# lpc_serial.net
KiCad netlist of a schematic drawn in EAGLE
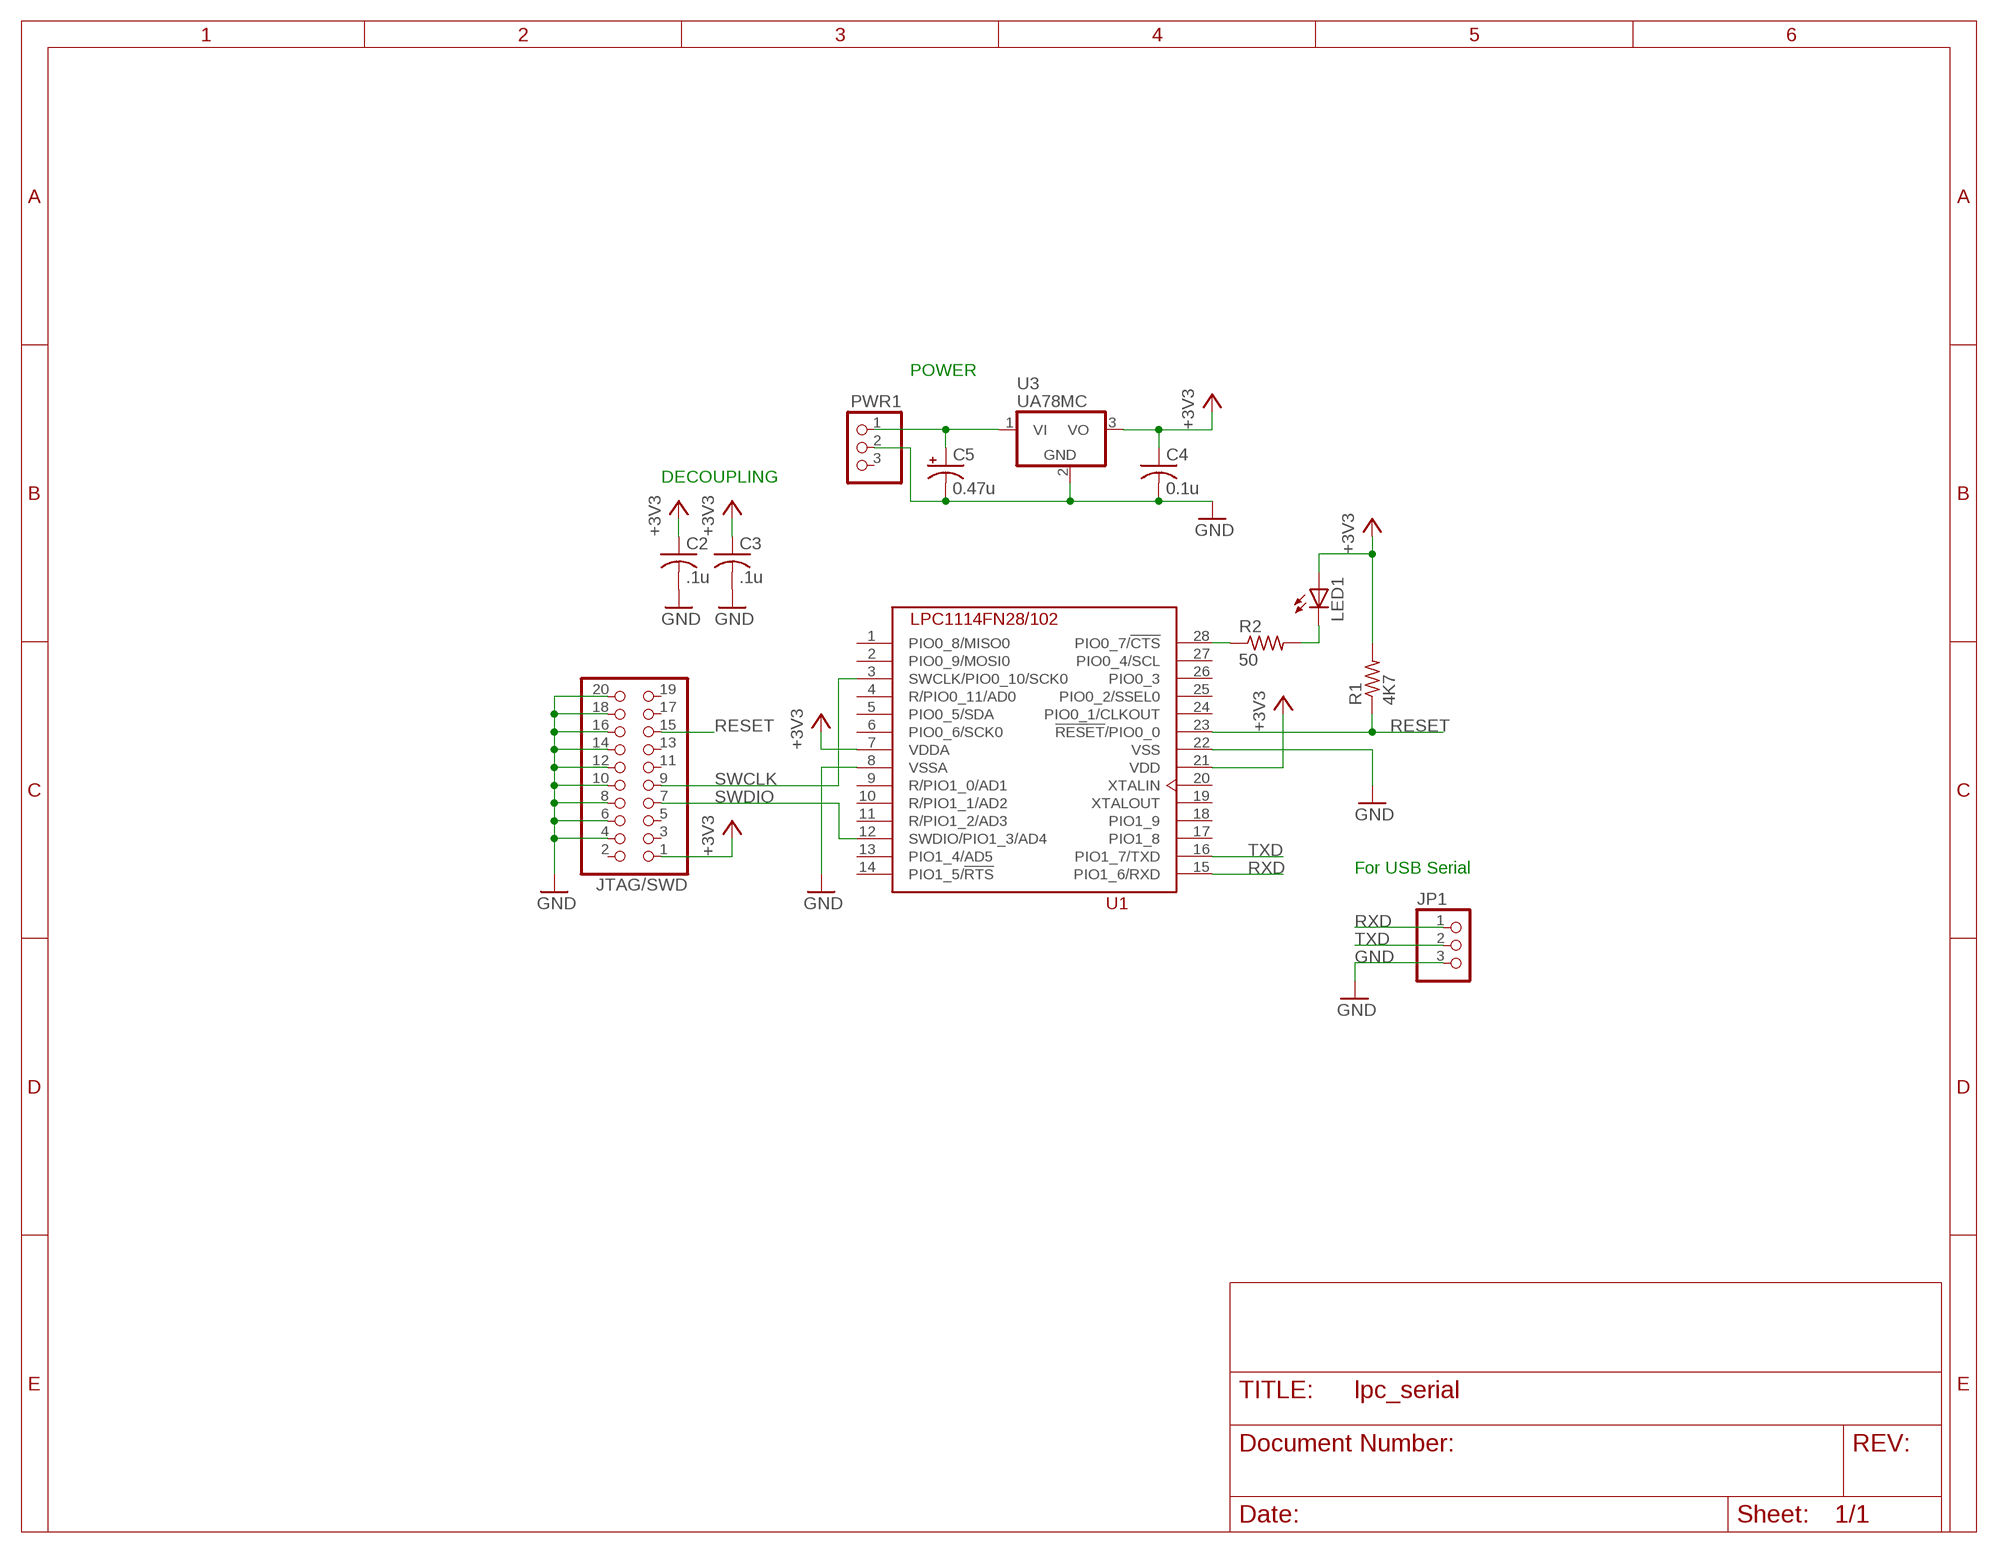
[diagram p0: schematic, sheet 1]

(export (version "E")
  (design (tool "Eeschema 10.0.6"))
  (components
    (comp (ref "C2")
      (value ".1u")
      (footprint "eagle-import:C050-024X044")
      (libsource (lib "eagle-import") (part "C-US050-024X044"))
    )
    (comp (ref "C3")
      (value ".1u")
      (footprint "eagle-import:C050-024X044")
      (libsource (lib "eagle-import") (part "C-US050-024X044"))
    )
    (comp (ref "C4")
      (value "0.1u")
      (footprint "eagle-import:C050-024X044")
      (libsource (lib "eagle-import") (part "C-US050-024X044"))
    )
    (comp (ref "C5")
      (value "0.47u")
      (footprint "eagle-import:E2-5")
      (libsource (lib "eagle-import") (part "CPOL-USE2-5"))
    )
    (comp (ref "JP1")
      (value "PINHD-1X3")
      (footprint "eagle-import:1X03")
      (libsource (lib "eagle-import") (part "PINHD-1X3"))
    )
    (comp (ref "JTAG/SWD")
      (value "PINHD-2X10")
      (footprint "eagle-import:2X10")
      (libsource (lib "eagle-import") (part "PINHD-2X10"))
    )
    (comp (ref "LED1")
      (value "LED10MM")
      (footprint "eagle-import:LED10MM")
      (libsource (lib "eagle-import") (part "LED10MM"))
    )
    (comp (ref "PWR1")
      (value "PINHD-1X3")
      (footprint "eagle-import:1X03")
      (libsource (lib "eagle-import") (part "PINHD-1X3"))
    )
    (comp (ref "R1")
      (value "4K7")
      (footprint "eagle-import:0207_10")
      (libsource (lib "eagle-import") (part "R-US_0207/10"))
    )
    (comp (ref "R2")
      (value "50")
      (footprint "eagle-import:0207_10")
      (libsource (lib "eagle-import") (part "R-US_0207/10"))
    )
    (comp (ref "U1")
      (value "LPC1114FN28/102")
      (footprint "eagle-import:DIL28-6")
      (libsource (lib "eagle-import") (part "LPC1114FN28/102"))
    )
    (comp (ref "U3")
      (value "UA78MC")
      (footprint "eagle-import:TO220V")
      (libsource (lib "eagle-import") (part "UA78MC"))
    )
  )
  (nets
    (net (code "1") (name "+3V3") (class "Default")
      (node (ref "C2") (pin "1") (pinfunction "1_1") (pintype "passive"))
      (node (ref "C3") (pin "1") (pinfunction "1_1") (pintype "passive"))
      (node (ref "C4") (pin "1") (pinfunction "1_1") (pintype "passive"))
      (node (ref "JTAG/SWD") (pin "1") (pinfunction "1_1") (pintype "passive"))
      (node (ref "LED1") (pin "A") (pinfunction "A_A") (pintype "passive"))
      (node (ref "R1") (pin "2") (pinfunction "2_2") (pintype "passive"))
      (node (ref "U1") (pin "21") (pinfunction "VDD_21") (pintype "power_in"))
      (node (ref "U1") (pin "7") (pinfunction "VDDA_7") (pintype "power_in"))
      (node (ref "U3") (pin "3") (pinfunction "VO_3") (pintype "passive"))
    )
    (net (code "2") (name "/RESET") (class "Default")
      (node (ref "JTAG/SWD") (pin "15") (pinfunction "15_15") (pintype "passive"))
      (node (ref "R1") (pin "1") (pinfunction "1_1") (pintype "passive"))
      (node (ref "U1") (pin "23") (pinfunction "~{RESET}/PIO0_0_23") (pintype "bidirectional"))
    )
    (net (code "3") (name "/RXD") (class "Default")
      (node (ref "JP1") (pin "1") (pinfunction "1_1") (pintype "passive"))
      (node (ref "U1") (pin "15") (pinfunction "PIO1_6/RXD_15") (pintype "bidirectional"))
    )
    (net (code "4") (name "/SWCLK") (class "Default")
      (node (ref "JTAG/SWD") (pin "9") (pinfunction "9_9") (pintype "passive"))
      (node (ref "U1") (pin "3") (pinfunction "SWCLK/PIO0_10/SCK0_3") (pintype "bidirectional"))
    )
    (net (code "5") (name "/SWDIO") (class "Default")
      (node (ref "JTAG/SWD") (pin "7") (pinfunction "7_7") (pintype "passive"))
      (node (ref "U1") (pin "12") (pinfunction "SWDIO/PIO1_3/AD4_12") (pintype "bidirectional"))
    )
    (net (code "6") (name "/TXD") (class "Default")
      (node (ref "JP1") (pin "2") (pinfunction "2_2") (pintype "passive"))
      (node (ref "U1") (pin "16") (pinfunction "PIO1_7/TXD_16") (pintype "bidirectional"))
    )
    (net (code "7") (name "GND") (class "Default")
      (node (ref "C2") (pin "2") (pinfunction "2_2") (pintype "passive"))
      (node (ref "C3") (pin "2") (pinfunction "2_2") (pintype "passive"))
      (node (ref "C4") (pin "2") (pinfunction "2_2") (pintype "passive"))
      (node (ref "C5") (pin "-") (pinfunction "-_-") (pintype "passive"))
      (node (ref "JP1") (pin "3") (pinfunction "3_3") (pintype "passive"))
      (node (ref "JTAG/SWD") (pin "10") (pinfunction "10_10") (pintype "passive"))
      (node (ref "JTAG/SWD") (pin "12") (pinfunction "12_12") (pintype "passive"))
      (node (ref "JTAG/SWD") (pin "14") (pinfunction "14_14") (pintype "passive"))
      (node (ref "JTAG/SWD") (pin "16") (pinfunction "16_16") (pintype "passive"))
      (node (ref "JTAG/SWD") (pin "18") (pinfunction "18_18") (pintype "passive"))
      (node (ref "JTAG/SWD") (pin "20") (pinfunction "20_20") (pintype "passive"))
      (node (ref "JTAG/SWD") (pin "4") (pinfunction "4_4") (pintype "passive"))
      (node (ref "JTAG/SWD") (pin "6") (pinfunction "6_6") (pintype "passive"))
      (node (ref "JTAG/SWD") (pin "8") (pinfunction "8_8") (pintype "passive"))
      (node (ref "PWR1") (pin "2") (pinfunction "2_2") (pintype "passive"))
      (node (ref "U1") (pin "22") (pinfunction "VSS_22") (pintype "power_in"))
      (node (ref "U1") (pin "8") (pinfunction "VSSA_8") (pintype "power_in"))
      (node (ref "U3") (pin "2") (pinfunction "GND_2") (pintype "passive"))
    )
    (net (code "8") (name "Net-(LED1-C)") (class "Default")
      (node (ref "LED1") (pin "K") (pinfunction "C_K") (pintype "passive"))
      (node (ref "R2") (pin "2") (pinfunction "2_2") (pintype "passive"))
    )
    (net (code "9") (name "Net-(U1-PIO0_7{slash}~{CTS})") (class "Default")
      (node (ref "R2") (pin "1") (pinfunction "1_1") (pintype "passive"))
      (node (ref "U1") (pin "28") (pinfunction "PIO0_7/~{CTS}_28") (pintype "bidirectional"))
    )
    (net (code "10") (name "Net-(U3-VI)") (class "Default")
      (node (ref "C5") (pin "+") (pinfunction "+_+") (pintype "passive"))
      (node (ref "PWR1") (pin "1") (pinfunction "1_1") (pintype "passive"))
      (node (ref "U3") (pin "1") (pinfunction "VI_1") (pintype "input"))
    )
    (net (code "11") (name "unconnected-(JTAG/SWD-Pad2)") (class "Default")
      (node (ref "JTAG/SWD") (pin "2") (pinfunction "2_2") (pintype "passive"))
    )
    (net (code "12") (name "unconnected-(JTAG/SWD-Pad3)") (class "Default")
      (node (ref "JTAG/SWD") (pin "3") (pinfunction "3_3") (pintype "passive"))
    )
    (net (code "13") (name "unconnected-(JTAG/SWD-Pad5)") (class "Default")
      (node (ref "JTAG/SWD") (pin "5") (pinfunction "5_5") (pintype "passive"))
    )
    (net (code "14") (name "unconnected-(JTAG/SWD-Pad11)") (class "Default")
      (node (ref "JTAG/SWD") (pin "11") (pinfunction "11_11") (pintype "passive"))
    )
    (net (code "15") (name "unconnected-(JTAG/SWD-Pad13)") (class "Default")
      (node (ref "JTAG/SWD") (pin "13") (pinfunction "13_13") (pintype "passive"))
    )
    (net (code "16") (name "unconnected-(JTAG/SWD-Pad17)") (class "Default")
      (node (ref "JTAG/SWD") (pin "17") (pinfunction "17_17") (pintype "passive"))
    )
    (net (code "17") (name "unconnected-(JTAG/SWD-Pad19)") (class "Default")
      (node (ref "JTAG/SWD") (pin "19") (pinfunction "19_19") (pintype "passive"))
    )
    (net (code "18") (name "unconnected-(PWR1-Pad3)") (class "Default")
      (node (ref "PWR1") (pin "3") (pinfunction "3_3") (pintype "passive"))
    )
    (net (code "19") (name "unconnected-(U1-PIO0_1{slash}CLKOUT-Pad24)") (class "Default")
      (node (ref "U1") (pin "24") (pinfunction "PIO0_1/CLKOUT_24") (pintype "bidirectional"))
    )
    (net (code "20") (name "unconnected-(U1-PIO0_2{slash}SSEL0-Pad25)") (class "Default")
      (node (ref "U1") (pin "25") (pinfunction "PIO0_2/SSEL0_25") (pintype "bidirectional"))
    )
    (net (code "21") (name "unconnected-(U1-PIO0_3-Pad26)") (class "Default")
      (node (ref "U1") (pin "26") (pinfunction "PIO0_3_26") (pintype "bidirectional"))
    )
    (net (code "22") (name "unconnected-(U1-PIO0_4{slash}SCL-Pad27)") (class "Default")
      (node (ref "U1") (pin "27") (pinfunction "PIO0_4/SCL_27") (pintype "bidirectional"))
    )
    (net (code "23") (name "unconnected-(U1-PIO0_5{slash}SDA-Pad5)") (class "Default")
      (node (ref "U1") (pin "5") (pinfunction "PIO0_5/SDA_5") (pintype "bidirectional"))
    )
    (net (code "24") (name "unconnected-(U1-PIO0_6{slash}SCK0-Pad6)") (class "Default")
      (node (ref "U1") (pin "6") (pinfunction "PIO0_6/SCK0_6") (pintype "bidirectional"))
    )
    (net (code "25") (name "unconnected-(U1-PIO0_8{slash}MISO0-Pad1)") (class "Default")
      (node (ref "U1") (pin "1") (pinfunction "PIO0_8/MISO0_1") (pintype "bidirectional"))
    )
    (net (code "26") (name "unconnected-(U1-PIO0_9{slash}MOSI0-Pad2)") (class "Default")
      (node (ref "U1") (pin "2") (pinfunction "PIO0_9/MOSI0_2") (pintype "bidirectional"))
    )
    (net (code "27") (name "unconnected-(U1-PIO1_4{slash}AD5-Pad13)") (class "Default")
      (node (ref "U1") (pin "13") (pinfunction "PIO1_4/AD5_13") (pintype "bidirectional"))
    )
    (net (code "28") (name "unconnected-(U1-PIO1_5{slash}~{RTS}-Pad14)") (class "Default")
      (node (ref "U1") (pin "14") (pinfunction "PIO1_5/~{RTS}_14") (pintype "bidirectional"))
    )
    (net (code "29") (name "unconnected-(U1-PIO1_8-Pad17)") (class "Default")
      (node (ref "U1") (pin "17") (pinfunction "PIO1_8_17") (pintype "bidirectional"))
    )
    (net (code "30") (name "unconnected-(U1-PIO1_9-Pad18)") (class "Default")
      (node (ref "U1") (pin "18") (pinfunction "PIO1_9_18") (pintype "bidirectional"))
    )
    (net (code "31") (name "unconnected-(U1-R{slash}PIO0_11{slash}AD0-Pad4)") (class "Default")
      (node (ref "U1") (pin "4") (pinfunction "R/PIO0_11/AD0_4") (pintype "bidirectional"))
    )
    (net (code "32") (name "unconnected-(U1-R{slash}PIO1_0{slash}AD1-Pad9)") (class "Default")
      (node (ref "U1") (pin "9") (pinfunction "R/PIO1_0/AD1_9") (pintype "bidirectional"))
    )
    (net (code "33") (name "unconnected-(U1-R{slash}PIO1_1{slash}AD2-Pad10)") (class "Default")
      (node (ref "U1") (pin "10") (pinfunction "R/PIO1_1/AD2_10") (pintype "bidirectional"))
    )
    (net (code "34") (name "unconnected-(U1-R{slash}PIO1_2{slash}AD3-Pad11)") (class "Default")
      (node (ref "U1") (pin "11") (pinfunction "R/PIO1_2/AD3_11") (pintype "bidirectional"))
    )
    (net (code "35") (name "unconnected-(U1-XTALIN-Pad20)") (class "Default")
      (node (ref "U1") (pin "20") (pinfunction "XTALIN_20") (pintype "bidirectional"))
    )
    (net (code "36") (name "unconnected-(U1-XTALOUT-Pad19)") (class "Default")
      (node (ref "U1") (pin "19") (pinfunction "XTALOUT_19") (pintype "output"))
    )
  )
)
